# MT3620_grove_breakout_v1_0.net
KiCad netlist of a schematic drawn in EAGLE
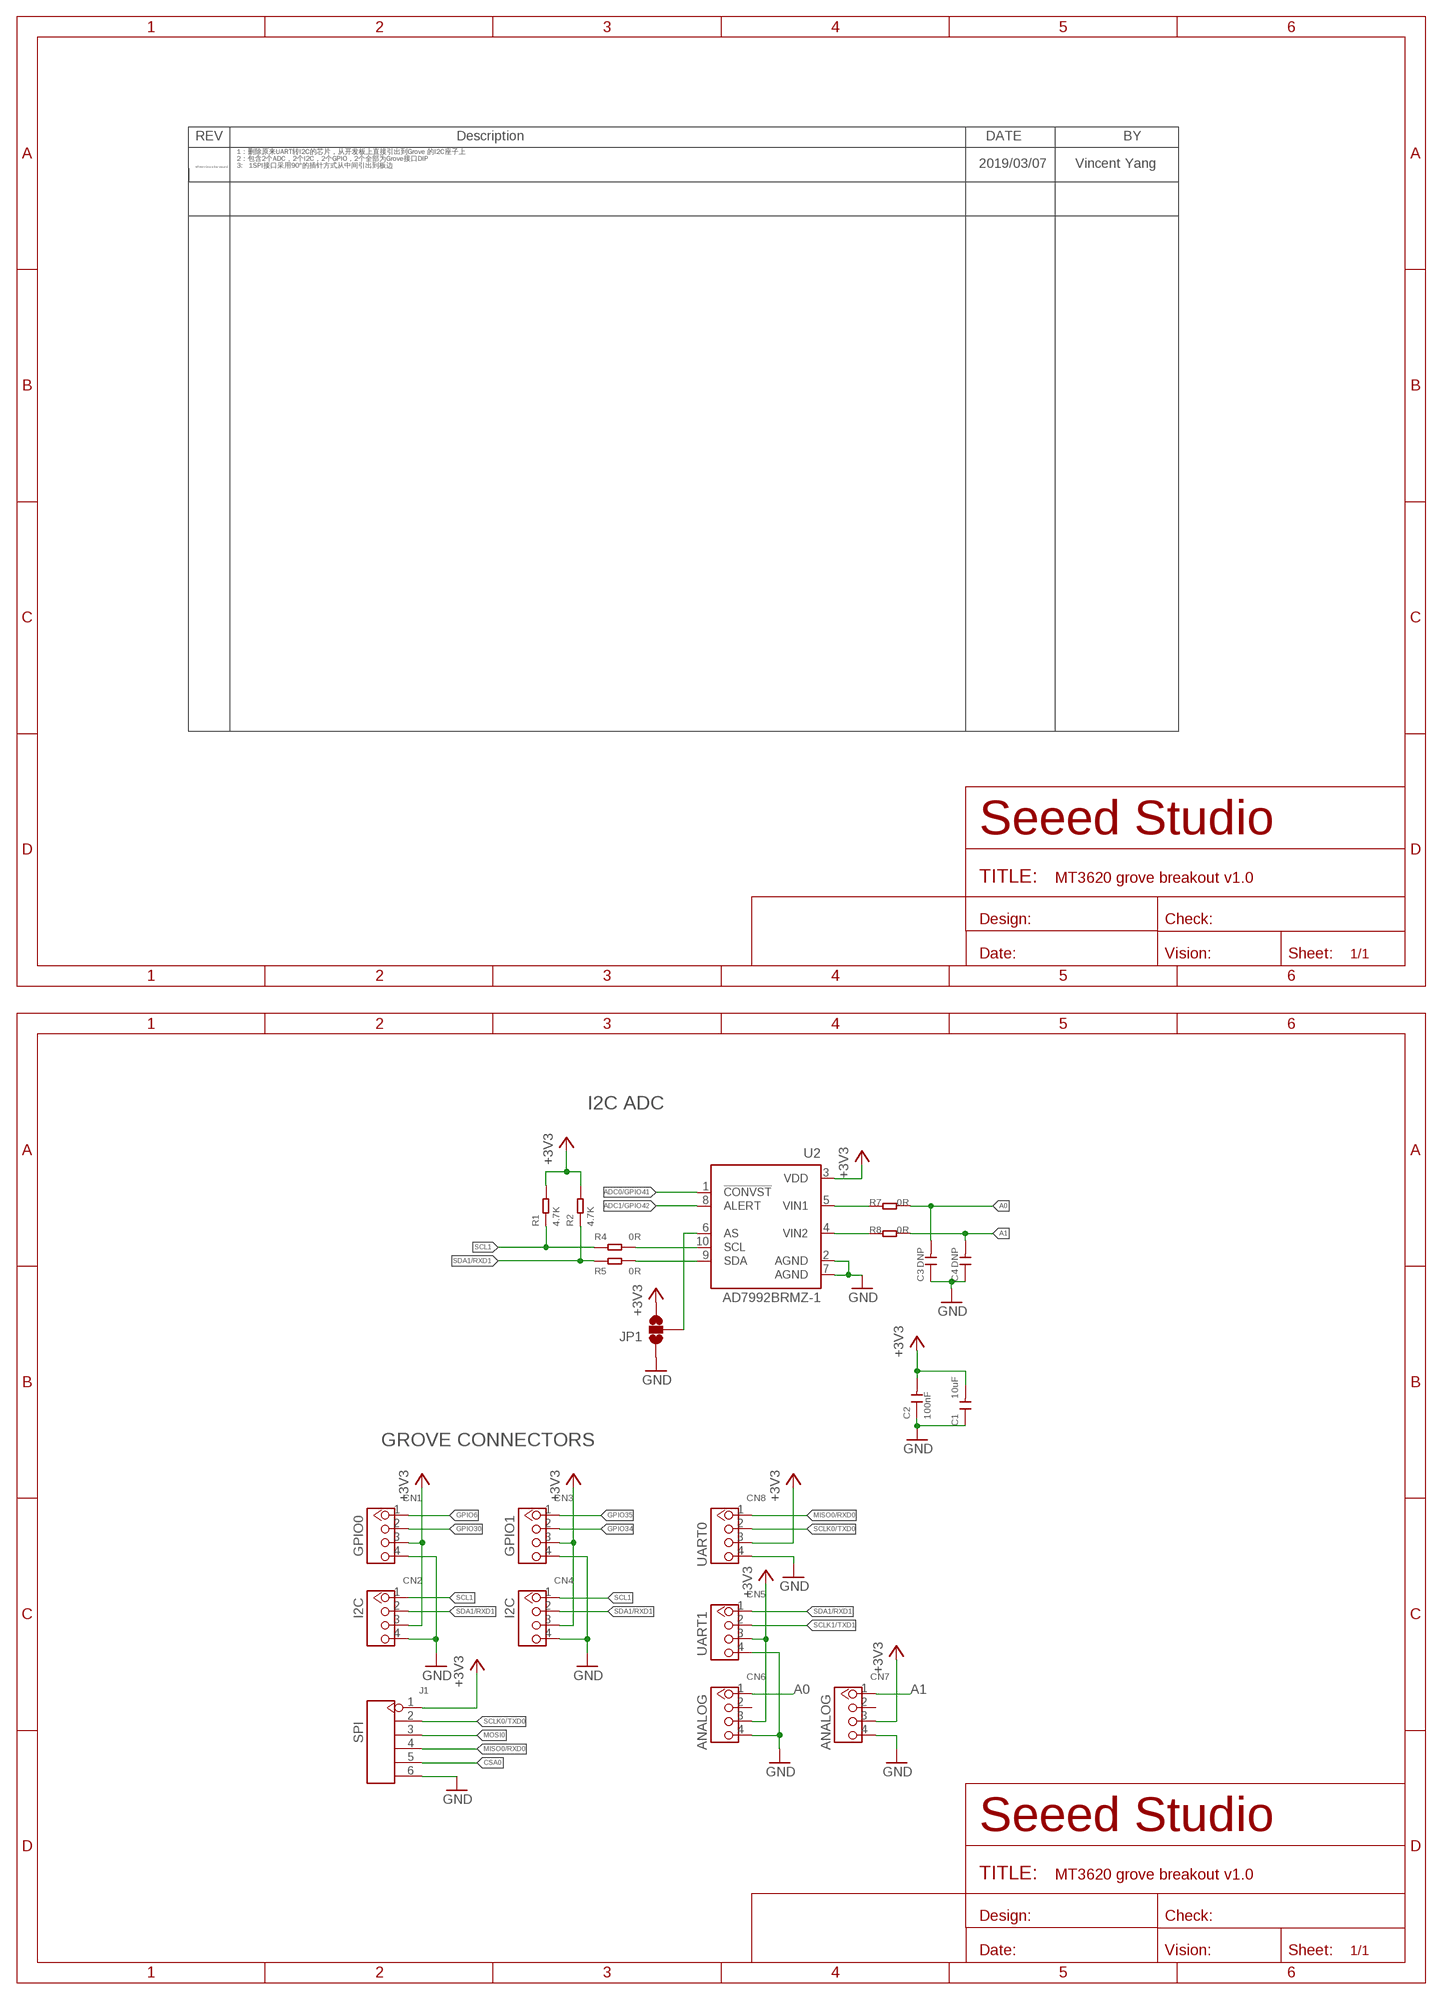
[diagram p0: schematic, sheet 1, part 1 of 2]
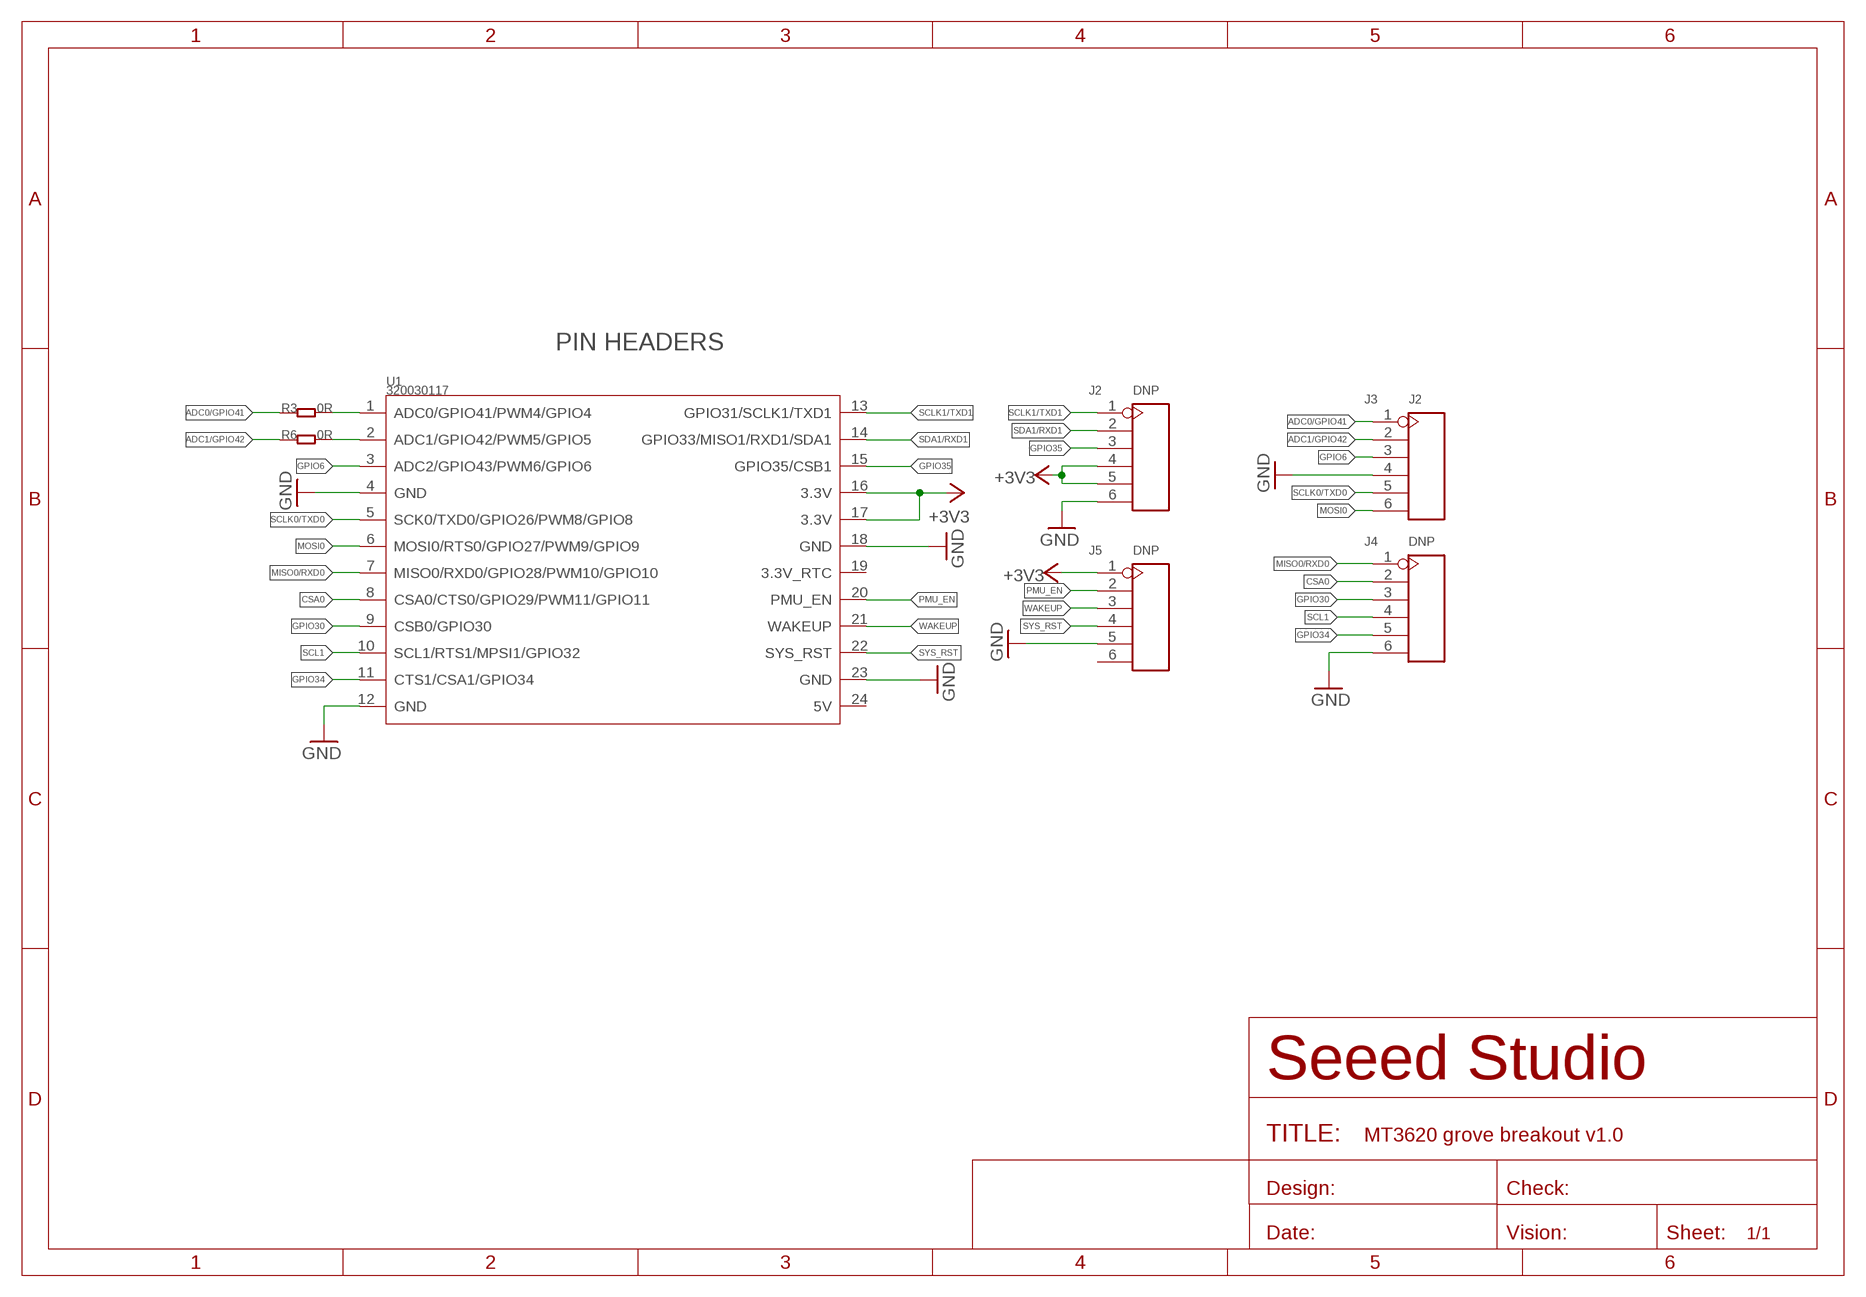
[diagram p1: schematic, sheet 1, part 2 of 2]

(export (version "E")
  (design (tool "Eeschema 10.0.6"))
  (components
    (comp (ref "C1")
      (value "10uF")
      (footprint "eagle-import:C0603")
      (libsource (lib "eagle-import") (part "CAP-0603"))
    )
    (comp (ref "C2")
      (value "100nF")
      (footprint "eagle-import:C0603")
      (libsource (lib "eagle-import") (part "CAP-0603"))
    )
    (comp (ref "C3")
      (value "DNP")
      (footprint "eagle-import:C0603")
      (libsource (lib "eagle-import") (part "CAP-0603"))
    )
    (comp (ref "C4")
      (value "DNP")
      (footprint "eagle-import:C0603")
      (libsource (lib "eagle-import") (part "CAP-0603"))
    )
    (comp (ref "CN1")
      (value "320110033")
      (footprint "eagle-import:HW4-2.0")
      (libsource (lib "eagle-import") (part "GROVE-CONNECTOR-DIP(4P-2.0)"))
    )
    (comp (ref "CN2")
      (value "320110033")
      (footprint "eagle-import:HW4-2.0")
      (libsource (lib "eagle-import") (part "GROVE-CONNECTOR-DIP(4P-2.0)"))
    )
    (comp (ref "CN3")
      (value "320110033")
      (footprint "eagle-import:HW4-2.0")
      (libsource (lib "eagle-import") (part "GROVE-CONNECTOR-DIP(4P-2.0)"))
    )
    (comp (ref "CN4")
      (value "320110033")
      (footprint "eagle-import:HW4-2.0")
      (libsource (lib "eagle-import") (part "GROVE-CONNECTOR-DIP(4P-2.0)"))
    )
    (comp (ref "CN5")
      (value "320110033")
      (footprint "eagle-import:HW4-2.0")
      (libsource (lib "eagle-import") (part "GROVE-CONNECTOR-DIP(4P-2.0)"))
    )
    (comp (ref "CN6")
      (value "320110033")
      (footprint "eagle-import:HW4-2.0")
      (libsource (lib "eagle-import") (part "GROVE-CONNECTOR-DIP(4P-2.0)"))
    )
    (comp (ref "CN7")
      (value "320110033")
      (footprint "eagle-import:HW4-2.0")
      (libsource (lib "eagle-import") (part "GROVE-CONNECTOR-DIP(4P-2.0)"))
    )
    (comp (ref "CN8")
      (value "320110033")
      (footprint "eagle-import:HW4-2.0")
      (libsource (lib "eagle-import") (part "GROVE-CONNECTOR-DIP(4P-2.0)"))
    )
    (comp (ref "J1")
      (value "320020019")
      (footprint "eagle-import:H6-2.54")
      (libsource (lib "eagle-import") (part "HEADER-6P-55/35MIL"))
    )
    (comp (ref "J2")
      (value "DNP")
      (footprint "eagle-import:H6-2.54")
      (libsource (lib "eagle-import") (part "HEADER-6P-55/35MIL"))
    )
    (comp (ref "J3")
      (value "J2")
      (footprint "eagle-import:H6-2.54")
      (libsource (lib "eagle-import") (part "HEADER-6P-55/35MIL"))
    )
    (comp (ref "J4")
      (value "DNP")
      (footprint "eagle-import:H6-2.54")
      (libsource (lib "eagle-import") (part "HEADER-6P-55/35MIL"))
    )
    (comp (ref "J5")
      (value "DNP")
      (footprint "eagle-import:H6-2.54")
      (libsource (lib "eagle-import") (part "HEADER-6P-55/35MIL"))
    )
    (comp (ref "JP1")
      (value "JUMPER-SMT_3_NO_SILK")
      (footprint "eagle-import:SMT-JUMPER_3_NO_SILK")
      (libsource (lib "eagle-import") (part "JUMPER-SMT_3_NO_SILK"))
    )
    (comp (ref "R1")
      (value "4.7K")
      (footprint "eagle-import:R0603")
      (libsource (lib "eagle-import") (part "RES-0603"))
    )
    (comp (ref "R2")
      (value "4.7K")
      (footprint "eagle-import:R0603")
      (libsource (lib "eagle-import") (part "RES-0603"))
    )
    (comp (ref "R3")
      (value "0R")
      (footprint "eagle-import:R0603")
      (libsource (lib "eagle-import") (part "RES-0603"))
    )
    (comp (ref "R4")
      (value "0R")
      (footprint "eagle-import:R0603")
      (libsource (lib "eagle-import") (part "RES-0603"))
    )
    (comp (ref "R5")
      (value "0R")
      (footprint "eagle-import:R0603")
      (libsource (lib "eagle-import") (part "RES-0603"))
    )
    (comp (ref "R6")
      (value "0R")
      (footprint "eagle-import:R0603")
      (libsource (lib "eagle-import") (part "RES-0603"))
    )
    (comp (ref "R7")
      (value "0R")
      (footprint "eagle-import:R0603")
      (libsource (lib "eagle-import") (part "RES-0603"))
    )
    (comp (ref "R8")
      (value "0R")
      (footprint "eagle-import:R0603")
      (libsource (lib "eagle-import") (part "RES-0603"))
    )
    (comp (ref "U1")
      (value "320030117")
      (footprint "eagle-import:MT3620-DEV-BOARD")
      (libsource (lib "eagle-import") (part "MT3620-DEV-BOARD"))
    )
    (comp (ref "U2")
      (value "AD7992BRMZ-1")
      (footprint "eagle-import:MSOP10")
      (fields (field (name "MPN") "AD7992BRMZ-0"))
      (libsource (lib "eagle-import") (part "AD7992"))
    )
  )
  (nets
    (net (code "1") (name "+3V3") (class "Default")
      (node (ref "C1") (pin "2") (pinfunction "2_2") (pintype "passive"))
      (node (ref "C2") (pin "2") (pinfunction "2_2") (pintype "passive"))
      (node (ref "CN1") (pin "3") (pinfunction "3_3") (pintype "bidirectional"))
      (node (ref "CN2") (pin "3") (pinfunction "3_3") (pintype "bidirectional"))
      (node (ref "CN3") (pin "3") (pinfunction "3_3") (pintype "bidirectional"))
      (node (ref "CN4") (pin "3") (pinfunction "3_3") (pintype "bidirectional"))
      (node (ref "CN5") (pin "3") (pinfunction "3_3") (pintype "bidirectional"))
      (node (ref "CN6") (pin "3") (pinfunction "3_3") (pintype "bidirectional"))
      (node (ref "CN7") (pin "3") (pinfunction "3_3") (pintype "bidirectional"))
      (node (ref "CN8") (pin "3") (pinfunction "3_3") (pintype "bidirectional"))
      (node (ref "J1") (pin "1") (pinfunction "1_1") (pintype "bidirectional"))
      (node (ref "J2") (pin "4") (pinfunction "4_4") (pintype "bidirectional"))
      (node (ref "J2") (pin "5") (pinfunction "5_5") (pintype "bidirectional"))
      (node (ref "J5") (pin "1") (pinfunction "1_1") (pintype "bidirectional"))
      (node (ref "JP1") (pin "1") (pinfunction "1_1") (pintype "passive"))
      (node (ref "R1") (pin "2") (pinfunction "2_2") (pintype "passive"))
      (node (ref "R2") (pin "2") (pinfunction "2_2") (pintype "passive"))
      (node (ref "U1") (pin "16") (pinfunction "3.3V_16") (pintype "bidirectional"))
      (node (ref "U1") (pin "17") (pinfunction "3.3V_17") (pintype "bidirectional"))
      (node (ref "U2") (pin "3") (pinfunction "VDD_3") (pintype "power_in"))
    )
    (net (code "2") (name "A0") (class "Default")
      (node (ref "C3") (pin "2") (pinfunction "2_2") (pintype "passive"))
      (node (ref "CN6") (pin "1") (pinfunction "1_1") (pintype "bidirectional"))
      (node (ref "R7") (pin "2") (pinfunction "2_2") (pintype "passive"))
    )
    (net (code "3") (name "A1") (class "Default")
      (node (ref "C4") (pin "2") (pinfunction "2_2") (pintype "passive"))
      (node (ref "CN7") (pin "1") (pinfunction "1_1") (pintype "bidirectional"))
      (node (ref "R8") (pin "2") (pinfunction "2_2") (pintype "passive"))
    )
    (net (code "4") (name "ADC0{slash}GPIO41") (class "Default")
      (node (ref "J3") (pin "1") (pinfunction "1_1") (pintype "bidirectional"))
      (node (ref "R3") (pin "2") (pinfunction "2_2") (pintype "passive"))
      (node (ref "U2") (pin "1") (pinfunction "~{CONVST}_1") (pintype "input"))
    )
    (net (code "5") (name "ADC1{slash}GPIO42") (class "Default")
      (node (ref "J3") (pin "2") (pinfunction "2_2") (pintype "bidirectional"))
      (node (ref "R6") (pin "2") (pinfunction "2_2") (pintype "passive"))
      (node (ref "U2") (pin "8") (pinfunction "ALERT_8") (pintype "output"))
    )
    (net (code "6") (name "CSA0") (class "Default")
      (node (ref "J1") (pin "5") (pinfunction "5_5") (pintype "bidirectional"))
      (node (ref "J4") (pin "2") (pinfunction "2_2") (pintype "bidirectional"))
      (node (ref "U1") (pin "8") (pinfunction "CSA0/CTS0/GPIO29/PWM11/GPIO11_8") (pintype "bidirectional"))
    )
    (net (code "7") (name "GND") (class "Default")
      (node (ref "C1") (pin "1") (pinfunction "1_1") (pintype "passive"))
      (node (ref "C2") (pin "1") (pinfunction "1_1") (pintype "passive"))
      (node (ref "C3") (pin "1") (pinfunction "1_1") (pintype "passive"))
      (node (ref "C4") (pin "1") (pinfunction "1_1") (pintype "passive"))
      (node (ref "CN1") (pin "4") (pinfunction "4_4") (pintype "bidirectional"))
      (node (ref "CN2") (pin "4") (pinfunction "4_4") (pintype "bidirectional"))
      (node (ref "CN3") (pin "4") (pinfunction "4_4") (pintype "bidirectional"))
      (node (ref "CN4") (pin "4") (pinfunction "4_4") (pintype "bidirectional"))
      (node (ref "CN5") (pin "4") (pinfunction "4_4") (pintype "bidirectional"))
      (node (ref "CN6") (pin "4") (pinfunction "4_4") (pintype "bidirectional"))
      (node (ref "CN7") (pin "4") (pinfunction "4_4") (pintype "bidirectional"))
      (node (ref "CN8") (pin "4") (pinfunction "4_4") (pintype "bidirectional"))
      (node (ref "J1") (pin "6") (pinfunction "6_6") (pintype "bidirectional"))
      (node (ref "J2") (pin "6") (pinfunction "6_6") (pintype "bidirectional"))
      (node (ref "J3") (pin "4") (pinfunction "4_4") (pintype "bidirectional"))
      (node (ref "J4") (pin "6") (pinfunction "6_6") (pintype "bidirectional"))
      (node (ref "J5") (pin "5") (pinfunction "5_5") (pintype "bidirectional"))
      (node (ref "JP1") (pin "3") (pinfunction "3_3") (pintype "passive"))
      (node (ref "U1") (pin "12") (pinfunction "GND_12") (pintype "bidirectional"))
      (node (ref "U1") (pin "18") (pinfunction "GND_18") (pintype "bidirectional"))
      (node (ref "U1") (pin "23") (pinfunction "GND_23") (pintype "bidirectional"))
      (node (ref "U1") (pin "4") (pinfunction "GND_4") (pintype "bidirectional"))
      (node (ref "U2") (pin "2") (pinfunction "AGND_2") (pintype "power_in"))
      (node (ref "U2") (pin "7") (pinfunction "AGND_7") (pintype "power_in"))
    )
    (net (code "8") (name "GPIO6") (class "Default")
      (node (ref "CN1") (pin "1") (pinfunction "1_1") (pintype "bidirectional"))
      (node (ref "J3") (pin "3") (pinfunction "3_3") (pintype "bidirectional"))
      (node (ref "U1") (pin "3") (pinfunction "ADC2/GPIO43/PWM6/GPIO6_3") (pintype "bidirectional"))
    )
    (net (code "9") (name "GPIO30") (class "Default")
      (node (ref "CN1") (pin "2") (pinfunction "2_2") (pintype "bidirectional"))
      (node (ref "J4") (pin "3") (pinfunction "3_3") (pintype "bidirectional"))
      (node (ref "U1") (pin "9") (pinfunction "CSB0/GPIO30_9") (pintype "bidirectional"))
    )
    (net (code "10") (name "GPIO34") (class "Default")
      (node (ref "CN3") (pin "2") (pinfunction "2_2") (pintype "bidirectional"))
      (node (ref "J4") (pin "5") (pinfunction "5_5") (pintype "bidirectional"))
      (node (ref "U1") (pin "11") (pinfunction "CTS1/CSA1/GPIO34_11") (pintype "bidirectional"))
    )
    (net (code "11") (name "GPIO35") (class "Default")
      (node (ref "CN3") (pin "1") (pinfunction "1_1") (pintype "bidirectional"))
      (node (ref "J2") (pin "3") (pinfunction "3_3") (pintype "bidirectional"))
      (node (ref "U1") (pin "15") (pinfunction "GPIO35/CSB1_15") (pintype "bidirectional"))
    )
    (net (code "12") (name "MISO0{slash}RXD0") (class "Default")
      (node (ref "CN8") (pin "1") (pinfunction "1_1") (pintype "bidirectional"))
      (node (ref "J1") (pin "4") (pinfunction "4_4") (pintype "bidirectional"))
      (node (ref "J4") (pin "1") (pinfunction "1_1") (pintype "bidirectional"))
      (node (ref "U1") (pin "7") (pinfunction "MISO0/RXD0/GPIO28/PWM10/GPIO10_7") (pintype "bidirectional"))
    )
    (net (code "13") (name "MOSI0") (class "Default")
      (node (ref "J1") (pin "3") (pinfunction "3_3") (pintype "bidirectional"))
      (node (ref "J3") (pin "6") (pinfunction "6_6") (pintype "bidirectional"))
      (node (ref "U1") (pin "6") (pinfunction "MOSI0/RTS0/GPIO27/PWM9/GPIO9_6") (pintype "bidirectional"))
    )
    (net (code "14") (name "Net-(U1-ADC0{slash}GPIO41{slash}PWM4{slash}GPIO4)") (class "Default")
      (node (ref "R3") (pin "1") (pinfunction "1_1") (pintype "passive"))
      (node (ref "U1") (pin "1") (pinfunction "ADC0/GPIO41/PWM4/GPIO4_1") (pintype "bidirectional"))
    )
    (net (code "15") (name "Net-(U1-ADC1{slash}GPIO42{slash}PWM5{slash}GPIO5)") (class "Default")
      (node (ref "R6") (pin "1") (pinfunction "1_1") (pintype "passive"))
      (node (ref "U1") (pin "2") (pinfunction "ADC1/GPIO42/PWM5/GPIO5_2") (pintype "bidirectional"))
    )
    (net (code "16") (name "Net-(U2-AS)") (class "Default")
      (node (ref "JP1") (pin "2") (pinfunction "2_2") (pintype "passive"))
      (node (ref "U2") (pin "6") (pinfunction "AS_6") (pintype "input"))
    )
    (net (code "17") (name "Net-(U2-SCL)") (class "Default")
      (node (ref "R4") (pin "2") (pinfunction "2_2") (pintype "passive"))
      (node (ref "U2") (pin "10") (pinfunction "SCL_10") (pintype "input"))
    )
    (net (code "18") (name "Net-(U2-SDA)") (class "Default")
      (node (ref "R5") (pin "2") (pinfunction "2_2") (pintype "passive"))
      (node (ref "U2") (pin "9") (pinfunction "SDA_9") (pintype "bidirectional"))
    )
    (net (code "19") (name "Net-(U2-VIN1)") (class "Default")
      (node (ref "R7") (pin "1") (pinfunction "1_1") (pintype "passive"))
      (node (ref "U2") (pin "5") (pinfunction "VIN1_5") (pintype "input"))
    )
    (net (code "20") (name "Net-(U2-VIN2)") (class "Default")
      (node (ref "R8") (pin "1") (pinfunction "1_1") (pintype "passive"))
      (node (ref "U2") (pin "4") (pinfunction "VIN2_4") (pintype "input"))
    )
    (net (code "21") (name "PMU_EN") (class "Default")
      (node (ref "J5") (pin "2") (pinfunction "2_2") (pintype "bidirectional"))
      (node (ref "U1") (pin "20") (pinfunction "PMU_EN_20") (pintype "bidirectional"))
    )
    (net (code "22") (name "SCL1") (class "Default")
      (node (ref "CN2") (pin "1") (pinfunction "1_1") (pintype "bidirectional"))
      (node (ref "CN4") (pin "1") (pinfunction "1_1") (pintype "bidirectional"))
      (node (ref "J4") (pin "4") (pinfunction "4_4") (pintype "bidirectional"))
      (node (ref "R1") (pin "1") (pinfunction "1_1") (pintype "passive"))
      (node (ref "R4") (pin "1") (pinfunction "1_1") (pintype "passive"))
      (node (ref "U1") (pin "10") (pinfunction "SCL1/RTS1/MPSI1/GPIO32_10") (pintype "bidirectional"))
    )
    (net (code "23") (name "SCLK0{slash}TXD0") (class "Default")
      (node (ref "CN8") (pin "2") (pinfunction "2_2") (pintype "bidirectional"))
      (node (ref "J1") (pin "2") (pinfunction "2_2") (pintype "bidirectional"))
      (node (ref "J3") (pin "5") (pinfunction "5_5") (pintype "bidirectional"))
      (node (ref "U1") (pin "5") (pinfunction "SCK0/TXD0/GPIO26/PWM8/GPIO8_5") (pintype "bidirectional"))
    )
    (net (code "24") (name "SCLK1{slash}TXD1") (class "Default")
      (node (ref "CN5") (pin "2") (pinfunction "2_2") (pintype "bidirectional"))
      (node (ref "J2") (pin "1") (pinfunction "1_1") (pintype "bidirectional"))
      (node (ref "U1") (pin "13") (pinfunction "GPIO31/SCLK1/TXD1_13") (pintype "bidirectional"))
    )
    (net (code "25") (name "SDA1{slash}RXD1") (class "Default")
      (node (ref "CN2") (pin "2") (pinfunction "2_2") (pintype "bidirectional"))
      (node (ref "CN4") (pin "2") (pinfunction "2_2") (pintype "bidirectional"))
      (node (ref "CN5") (pin "1") (pinfunction "1_1") (pintype "bidirectional"))
      (node (ref "J2") (pin "2") (pinfunction "2_2") (pintype "bidirectional"))
      (node (ref "R2") (pin "1") (pinfunction "1_1") (pintype "passive"))
      (node (ref "R5") (pin "1") (pinfunction "1_1") (pintype "passive"))
      (node (ref "U1") (pin "14") (pinfunction "GPIO33/MISO1/RXD1/SDA1_14") (pintype "bidirectional"))
    )
    (net (code "26") (name "SYS_RST") (class "Default")
      (node (ref "J5") (pin "4") (pinfunction "4_4") (pintype "bidirectional"))
      (node (ref "U1") (pin "22") (pinfunction "SYS_RST_22") (pintype "bidirectional"))
    )
    (net (code "27") (name "WAKEUP") (class "Default")
      (node (ref "J5") (pin "3") (pinfunction "3_3") (pintype "bidirectional"))
      (node (ref "U1") (pin "21") (pinfunction "WAKEUP_21") (pintype "bidirectional"))
    )
    (net (code "28") (name "unconnected-(CN6-Pad2)") (class "Default")
      (node (ref "CN6") (pin "2") (pinfunction "2_2") (pintype "bidirectional"))
    )
    (net (code "29") (name "unconnected-(CN7-Pad2)") (class "Default")
      (node (ref "CN7") (pin "2") (pinfunction "2_2") (pintype "bidirectional"))
    )
    (net (code "30") (name "unconnected-(J5-Pad6)") (class "Default")
      (node (ref "J5") (pin "6") (pinfunction "6_6") (pintype "bidirectional"))
    )
    (net (code "31") (name "unconnected-(U1-3.3V_RTC-Pad19)") (class "Default")
      (node (ref "U1") (pin "19") (pinfunction "3.3V_RTC_19") (pintype "bidirectional"))
    )
    (net (code "32") (name "unconnected-(U1-5V-Pad24)") (class "Default")
      (node (ref "U1") (pin "24") (pinfunction "5V_24") (pintype "bidirectional"))
    )
  )
)
